# Delay_latch_stage.net
KiCad netlist of a schematic drawn in Altium Designer
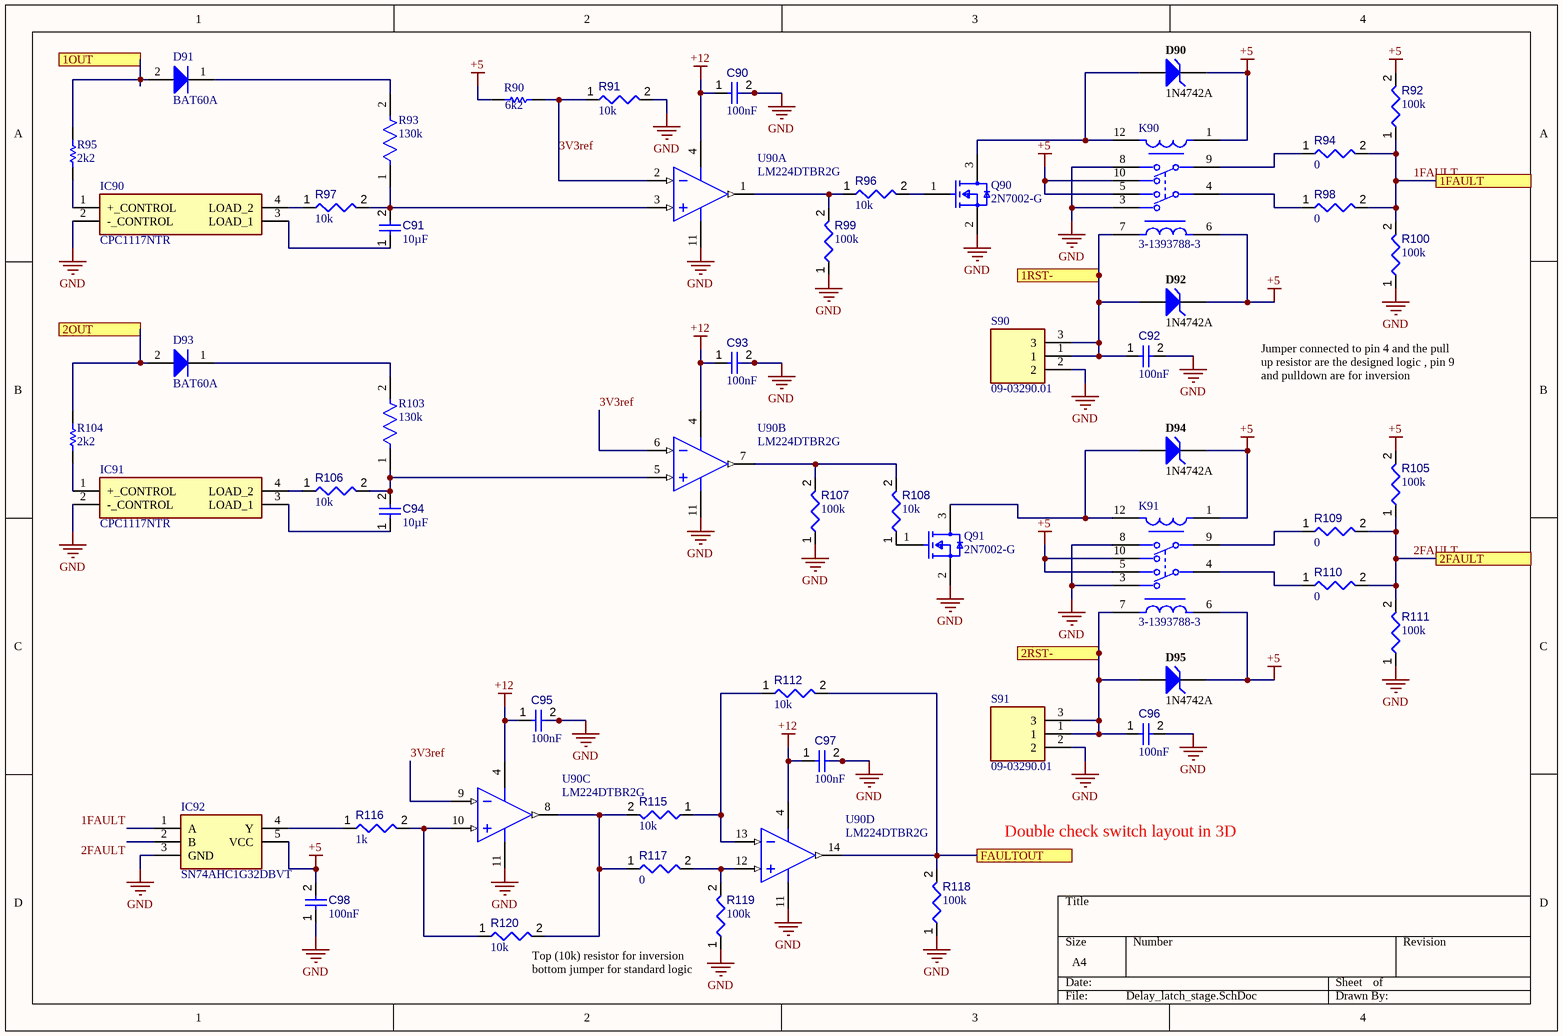
[diagram p0: Delay_latch_stage.SchDoc]

(export (version "E")
  (design (tool "Eeschema 10.0.6"))
  (components
    (comp (ref "C90")
      (value "100nF")
      (footprint "CAPC1608X90X40NL10T20")
      (description "Chip Capacitor, 100 nF, +/- 10%, 50 V, 0603 (1608 Metric)")
      (fields (field (name "TOLERANCE") "10%") (field (name "Comment") "Capacitor 100 nF +/-10% 50 V 0603"))
      (libsource (lib "UNSW Redback Racing") (part "CAP-NP-2"))
    )
    (comp (ref "C91")
      (value "10µF")
      (footprint "CAPC0603(1608)100_L")
      (description "Chip Capacitor, 10µF +/-20%, 10V, 0603, Thickness 1 mm")
      (fields (field (name "TOLERANCE") "10%") (field (name "Comment") "Capacitor 10µF +/-20% 10V 0603"))
      (libsource (lib "UNSW Redback Racing") (part "CAP-NP-2"))
    )
    (comp (ref "C92")
      (value "100nF")
      (footprint "CAPC1608X90X40NL10T20")
      (description "Chip Capacitor, 100 nF, +/- 10%, 50 V, 0603 (1608 Metric)")
      (fields (field (name "TOLERANCE") "10%") (field (name "Comment") "Capacitor 100 nF +/-10% 50 V 0603"))
      (libsource (lib "UNSW Redback Racing") (part "CAP-NP-2"))
    )
    (comp (ref "C93")
      (value "100nF")
      (footprint "CAPC1608X90X40NL10T20")
      (description "Chip Capacitor, 100 nF, +/- 10%, 50 V, 0603 (1608 Metric)")
      (fields (field (name "TOLERANCE") "10%") (field (name "Comment") "Capacitor 100 nF +/-10% 50 V 0603"))
      (libsource (lib "UNSW Redback Racing") (part "CAP-NP-2"))
    )
    (comp (ref "C94")
      (value "10µF")
      (footprint "CAPC0603(1608)100_L")
      (description "Chip Capacitor, 10µF +/-20%, 10V, 0603, Thickness 1 mm")
      (fields (field (name "TOLERANCE") "10%") (field (name "Comment") "Capacitor 10µF +/-20% 10V 0603"))
      (libsource (lib "UNSW Redback Racing") (part "CAP-NP-2"))
    )
    (comp (ref "C95")
      (value "100nF")
      (footprint "CAPC1608X90X40NL10T20")
      (description "Chip Capacitor, 100 nF, +/- 10%, 50 V, 0603 (1608 Metric)")
      (fields (field (name "TOLERANCE") "10%") (field (name "Comment") "Capacitor 100 nF +/-10% 50 V 0603"))
      (libsource (lib "UNSW Redback Racing") (part "CAP-NP-2"))
    )
    (comp (ref "C96")
      (value "100nF")
      (footprint "CAPC1608X90X40NL10T20")
      (description "Chip Capacitor, 100 nF, +/- 10%, 50 V, 0603 (1608 Metric)")
      (fields (field (name "TOLERANCE") "10%") (field (name "Comment") "Capacitor 100 nF +/-10% 50 V 0603"))
      (libsource (lib "UNSW Redback Racing") (part "CAP-NP-2"))
    )
    (comp (ref "C97")
      (value "100nF")
      (footprint "CAPC1608X90X40NL10T20")
      (description "Chip Capacitor, 100 nF, +/- 10%, 50 V, 0603 (1608 Metric)")
      (fields (field (name "TOLERANCE") "10%") (field (name "Comment") "Capacitor 100 nF +/-10% 50 V 0603"))
      (libsource (lib "UNSW Redback Racing") (part "CAP-NP-2"))
    )
    (comp (ref "C98")
      (value "100nF")
      (footprint "CAPC1608X90X40NL10T20")
      (description "Chip Capacitor, 100 nF, +/- 10%, 50 V, 0603 (1608 Metric)")
      (fields (field (name "TOLERANCE") "10%") (field (name "Comment") "Capacitor 100 nF +/-10% 50 V 0603"))
      (libsource (lib "UNSW Redback Racing") (part "CAP-NP-2"))
    )
    (comp (ref "D90")
      (value "1N4742A")
      (footprint "FAIR-DO-41-2_V")
      (description "Zener Diode, 12V, 1W, 5%, -65 to 200 degC, 2-Pin DO-41, Body 2.72 x 5.2 mm, RoHS")
      (fields (field (name "TOLERANCE") "5%") (field (name "MANUFACTURER") "Fairchild Semiconductor"))
      (libsource (lib "Altium Content Vault") (part "FAIR-DZEN-A1K2-2"))
    )
    (comp (ref "D91")
      (value "BAT60A")
      (footprint "INF-SOD323_V")
      (description "Silicon Schottky Diode, -55 to 85 degC, SOD323, Reel, Green")
      (fields (field (name "MANUFACTURER") "Infineon"))
      (libsource (lib "Altium Content Vault") (part "INF-D_K1A2-2"))
    )
    (comp (ref "D92")
      (value "1N4742A")
      (footprint "FAIR-DO-41-2_V")
      (description "Zener Diode, 12V, 1W, 5%, -65 to 200 degC, 2-Pin DO-41, Body 2.72 x 5.2 mm, RoHS")
      (fields (field (name "TOLERANCE") "5%") (field (name "MANUFACTURER") "Fairchild Semiconductor"))
      (libsource (lib "Altium Content Vault") (part "FAIR-DZEN-A1K2-2"))
    )
    (comp (ref "D93")
      (value "BAT60A")
      (footprint "INF-SOD323_V")
      (description "Silicon Schottky Diode, -55 to 85 degC, SOD323, Reel, Green")
      (fields (field (name "MANUFACTURER") "Infineon"))
      (libsource (lib "Altium Content Vault") (part "INF-D_K1A2-2"))
    )
    (comp (ref "D94")
      (value "1N4742A")
      (footprint "FAIR-DO-41-2_V")
      (description "Zener Diode, 12V, 1W, 5%, -65 to 200 degC, 2-Pin DO-41, Body 2.72 x 5.2 mm, RoHS")
      (fields (field (name "TOLERANCE") "5%") (field (name "MANUFACTURER") "Fairchild Semiconductor"))
      (libsource (lib "Altium Content Vault") (part "FAIR-DZEN-A1K2-2"))
    )
    (comp (ref "D95")
      (value "1N4742A")
      (footprint "FAIR-DO-41-2_V")
      (description "Zener Diode, 12V, 1W, 5%, -65 to 200 degC, 2-Pin DO-41, Body 2.72 x 5.2 mm, RoHS")
      (fields (field (name "TOLERANCE") "5%") (field (name "MANUFACTURER") "Fairchild Semiconductor"))
      (libsource (lib "Altium Content Vault") (part "FAIR-DZEN-A1K2-2"))
    )
    (comp (ref "IC90")
      (value "CPC1117NTR")
      (footprint "SamacSys:SOP254P610X216-4N")
      (description "Integrated Circuit")
      (fields (field (name "MOUSER2 PART NUMBER") "849-CPC1117NTR"))
      (libsource (lib "*") (part "CPC1117NTR"))
    )
    (comp (ref "IC91")
      (value "CPC1117NTR")
      (footprint "SamacSys:SOP254P610X216-4N")
      (description "Integrated Circuit")
      (fields (field (name "MOUSER2 PART NUMBER") "849-CPC1117NTR"))
      (libsource (lib "*") (part "CPC1117NTR"))
    )
    (comp (ref "IC92")
      (value "SN74AHC1G32DBVT")
      (footprint "SamacSys:SOT95P280X145-5N")
      (description "Integrated Circuit")
      (fields (field (name "MOUSER PART NUMBER") "595-SN74AHC1G32DBVT"))
      (libsource (lib "*") (part "SN74AHC1G32DBVT"))
    )
    (comp (ref "K90")
      (value "3-1393788-3")
      (footprint "FP-3-1393788-3-MFG")
      (description "RELAY GEN PURPOSE DPDT 2A 5VDC")
      (fields
        (field (name "OCTOPART") "https://octopart.com/3-1393788-3-te+connectivity-40665546")
        (field (name "MANUFACTURER") "TE Connectivity")
      )
      (libsource (lib "Altium Content Vault") (part "ac98cbd59e0863ff6ea4ecacfdd74e3"))
    )
    (comp (ref "K91")
      (value "3-1393788-3")
      (footprint "FP-3-1393788-3-MFG")
      (description "RELAY GEN PURPOSE DPDT 2A 5VDC")
      (fields
        (field (name "OCTOPART") "https://octopart.com/3-1393788-3-te+connectivity-40665546")
        (field (name "MANUFACTURER") "TE Connectivity")
      )
      (libsource (lib "Altium Content Vault") (part "ac98cbd59e0863ff6ea4ecacfdd74e3"))
    )
    (comp (ref "Q90")
      (value "2N7002-G")
      (footprint "FP-2N7002-G-IPC_C")
      (description "MOSFET N-CH 60V 0.115A SOT23-3")
      (fields
        (field (name "OCTOPART") "https://octopart.com/2n7002-g-microchip-47153309")
        (field (name "MANUFACTURER") "Microchip")
      )
      (libsource (lib "Altium Content Vault") (part "e719174c72bdd709d73c8feae40c216"))
    )
    (comp (ref "Q91")
      (value "2N7002-G")
      (footprint "FP-2N7002-G-IPC_C")
      (description "MOSFET N-CH 60V 0.115A SOT23-3")
      (fields
        (field (name "OCTOPART") "https://octopart.com/2n7002-g-microchip-47153309")
        (field (name "MANUFACTURER") "Microchip")
      )
      (libsource (lib "Altium Content Vault") (part "e719174c72bdd709d73c8feae40c216"))
    )
    (comp (ref "R90")
      (value "6k2")
      (footprint "RESC1609X50X30ML10T20")
      (fields (field (name "PART NUMBER") "CRCW06036K20FKEA") (field (name "MANUFACTURER") "Vishay Dale"))
      (libsource (lib "Altium Content Vault") (part "RES"))
    )
    (comp (ref "R91")
      (value "10k")
      (footprint "RESC1608X55X25ML10T15")
      (description "Chip Resistor, 10 KOhm, +/- 1%, 01 W, -55 to 155 degC, 0603 (1608 Metric)")
      (fields (field (name "POWER") "100mW") (field (name "TOLERANCE") "1%"))
      (libsource (lib "UNSW Redback Racing") (part "RES-2"))
    )
    (comp (ref "R92")
      (value "100k")
      (footprint "RESC1608X55X25ML10T15")
      (description "Chip Resistor, 100 KOhm, +/- 1%, 0.1 W, -55 to 155 degC, 0603 (1608 Metric)")
      (fields (field (name "TOLERANCE") "1%") (field (name "POWER") "100mW"))
      (libsource (lib "UNSW Redback Racing") (part "RES-2"))
    )
    (comp (ref "R93")
      (value "130k")
      (footprint "FP-CRCW0603-e3-IPC_C")
      (description "RES Thick Film, 130kΩ, 1%, 0.1W, 100ppm/°C, 0603")
      (fields (field (name "TOLERANCE") "1%"))
      (libsource (lib "Altium Content Vault") (part "1029c3af85768c4190bb7ad29bc67b5"))
    )
    (comp (ref "R94")
      (value "0")
      (footprint "RESC0603(1608)_L")
      (description "Jumper 0603 (1608 Metric)")
      (fields (field (name "Comment") "0R3J"))
      (libsource (lib "UNSW Redback Racing") (part "0R3J"))
    )
    (comp (ref "R95")
      (value "2k2")
      (footprint "RESC1608X55X25LL10T15")
      (fields (field (name "TOLERANCE") "1%") (field (name "MANUFACTURER") "Yageo"))
      (libsource (lib "Altium Content Vault") (part "RES-2"))
    )
    (comp (ref "R96")
      (value "10k")
      (footprint "RESC1608X55X25ML10T15")
      (description "Chip Resistor, 10 KOhm, +/- 1%, 01 W, -55 to 155 degC, 0603 (1608 Metric)")
      (fields (field (name "POWER") "100mW") (field (name "TOLERANCE") "1%"))
      (libsource (lib "UNSW Redback Racing") (part "RES-2"))
    )
    (comp (ref "R97")
      (value "10k")
      (footprint "RESC1608X55X25ML10T15")
      (description "Chip Resistor, 10 KOhm, +/- 1%, 01 W, -55 to 155 degC, 0603 (1608 Metric)")
      (fields (field (name "POWER") "100mW") (field (name "TOLERANCE") "1%"))
      (libsource (lib "UNSW Redback Racing") (part "RES-2"))
    )
    (comp (ref "R98")
      (value "0")
      (footprint "RESC0603(1608)_L")
      (description "Jumper 0603 (1608 Metric)")
      (fields (field (name "Comment") "0R3J"))
      (libsource (lib "UNSW Redback Racing") (part "0R3J"))
    )
    (comp (ref "R99")
      (value "100k")
      (footprint "RESC1608X55X25ML10T15")
      (description "Chip Resistor, 100 KOhm, +/- 1%, 0.1 W, -55 to 155 degC, 0603 (1608 Metric)")
      (fields (field (name "TOLERANCE") "1%") (field (name "POWER") "100mW"))
      (libsource (lib "UNSW Redback Racing") (part "RES-2"))
    )
    (comp (ref "R100")
      (value "100k")
      (footprint "RESC1608X55X25ML10T15")
      (description "Chip Resistor, 100 KOhm, +/- 1%, 0.1 W, -55 to 155 degC, 0603 (1608 Metric)")
      (fields (field (name "TOLERANCE") "1%") (field (name "POWER") "100mW"))
      (libsource (lib "UNSW Redback Racing") (part "RES-2"))
    )
    (comp (ref "R103")
      (value "130k")
      (footprint "FP-CRCW0603-e3-IPC_C")
      (description "RES Thick Film, 130kΩ, 1%, 0.1W, 100ppm/°C, 0603")
      (fields (field (name "TOLERANCE") "1%"))
      (libsource (lib "Altium Content Vault") (part "1029c3af85768c4190bb7ad29bc67b5"))
    )
    (comp (ref "R104")
      (value "2k2")
      (footprint "RESC1608X55X25LL10T15")
      (fields (field (name "TOLERANCE") "1%") (field (name "MANUFACTURER") "Yageo"))
      (libsource (lib "Altium Content Vault") (part "RES-2"))
    )
    (comp (ref "R105")
      (value "100k")
      (footprint "RESC1608X55X25ML10T15")
      (description "Chip Resistor, 100 KOhm, +/- 1%, 0.1 W, -55 to 155 degC, 0603 (1608 Metric)")
      (fields (field (name "TOLERANCE") "1%") (field (name "POWER") "100mW"))
      (libsource (lib "UNSW Redback Racing") (part "RES-2"))
    )
    (comp (ref "R106")
      (value "10k")
      (footprint "RESC1608X55X25ML10T15")
      (description "Chip Resistor, 10 KOhm, +/- 1%, 01 W, -55 to 155 degC, 0603 (1608 Metric)")
      (fields (field (name "POWER") "100mW") (field (name "TOLERANCE") "1%"))
      (libsource (lib "UNSW Redback Racing") (part "RES-2"))
    )
    (comp (ref "R107")
      (value "100k")
      (footprint "RESC1608X55X25ML10T15")
      (description "Chip Resistor, 100 KOhm, +/- 1%, 0.1 W, -55 to 155 degC, 0603 (1608 Metric)")
      (fields (field (name "TOLERANCE") "1%") (field (name "POWER") "100mW"))
      (libsource (lib "UNSW Redback Racing") (part "RES-2"))
    )
    (comp (ref "R108")
      (value "10k")
      (footprint "RESC1608X55X25ML10T15")
      (description "Chip Resistor, 10 KOhm, +/- 1%, 01 W, -55 to 155 degC, 0603 (1608 Metric)")
      (fields (field (name "POWER") "100mW") (field (name "TOLERANCE") "1%"))
      (libsource (lib "UNSW Redback Racing") (part "RES-2"))
    )
    (comp (ref "R109")
      (value "0")
      (footprint "RESC0603(1608)_L")
      (description "Jumper 0603 (1608 Metric)")
      (fields (field (name "Comment") "0R3J"))
      (libsource (lib "UNSW Redback Racing") (part "0R3J"))
    )
    (comp (ref "R110")
      (value "0")
      (footprint "RESC0603(1608)_L")
      (description "Jumper 0603 (1608 Metric)")
      (fields (field (name "Comment") "0R3J"))
      (libsource (lib "UNSW Redback Racing") (part "0R3J"))
    )
    (comp (ref "R111")
      (value "100k")
      (footprint "RESC1608X55X25ML10T15")
      (description "Chip Resistor, 100 KOhm, +/- 1%, 0.1 W, -55 to 155 degC, 0603 (1608 Metric)")
      (fields (field (name "TOLERANCE") "1%") (field (name "POWER") "100mW"))
      (libsource (lib "UNSW Redback Racing") (part "RES-2"))
    )
    (comp (ref "R112")
      (value "10k")
      (footprint "RESC1608X55X25ML10T15")
      (description "Chip Resistor, 10 KOhm, +/- 1%, 01 W, -55 to 155 degC, 0603 (1608 Metric)")
      (fields (field (name "POWER") "100mW") (field (name "TOLERANCE") "1%"))
      (libsource (lib "UNSW Redback Racing") (part "RES-2"))
    )
    (comp (ref "R115")
      (value "10k")
      (footprint "RESC1608X55X25ML10T15")
      (description "Chip Resistor, 10 KOhm, +/- 1%, 01 W, -55 to 155 degC, 0603 (1608 Metric)")
      (fields (field (name "POWER") "100mW") (field (name "TOLERANCE") "1%"))
      (libsource (lib "UNSW Redback Racing") (part "RES-2"))
    )
    (comp (ref "R116")
      (value "1k")
      (footprint "RESC1608X55X25ML10T15")
      (description "Chip Resistor, 1 KOhm, +/-1%, 0.1 W, -55 to 155 degC, 0603 (1608 Metric)")
      (fields (field (name "POWER") "100mW") (field (name "TOLERANCE") "1%"))
      (libsource (lib "UNSW Redback Racing") (part "RES-2"))
    )
    (comp (ref "R117")
      (value "0")
      (footprint "RESC0603(1608)_L")
      (description "Jumper 0603 (1608 Metric)")
      (fields (field (name "Comment") "0R3J"))
      (libsource (lib "UNSW Redback Racing") (part "0R3J"))
    )
    (comp (ref "R118")
      (value "100k")
      (footprint "RESC1608X55X25ML10T15")
      (description "Chip Resistor, 100 KOhm, +/- 1%, 0.1 W, -55 to 155 degC, 0603 (1608 Metric)")
      (fields (field (name "TOLERANCE") "1%") (field (name "POWER") "100mW"))
      (libsource (lib "UNSW Redback Racing") (part "RES-2"))
    )
    (comp (ref "R119")
      (value "100k")
      (footprint "RESC1608X55X25ML10T15")
      (description "Chip Resistor, 100 KOhm, +/- 1%, 0.1 W, -55 to 155 degC, 0603 (1608 Metric)")
      (fields (field (name "TOLERANCE") "1%") (field (name "POWER") "100mW"))
      (libsource (lib "UNSW Redback Racing") (part "RES-2"))
    )
    (comp (ref "R120")
      (value "10k")
      (footprint "RESC1608X55X25ML10T15")
      (description "Chip Resistor, 10 KOhm, +/- 1%, 01 W, -55 to 155 degC, 0603 (1608 Metric)")
      (fields (field (name "POWER") "100mW") (field (name "TOLERANCE") "1%"))
      (libsource (lib "UNSW Redback Racing") (part "RES-2"))
    )
    (comp (ref "S90")
      (value "09-03290.01")
      (footprint "SamacSys:09.03290.01")
      (description "Switch")
      (libsource (lib "*") (part "09-03290.01"))
    )
    (comp (ref "S91")
      (value "09-03290.01")
      (footprint "SamacSys:09.03290.01")
      (description "Switch")
      (libsource (lib "*") (part "09-03290.01"))
    )
    (comp (ref "U90")
      (value "LM224DTBR2G")
      (footprint "ONSC-TSSOP-14-948G-01_V")
      (fields (field (name "MANUFACTURER") "On Semiconductor"))
      (libsource (lib "Altium Content Vault") (part "ONSC-LM224_324_2902_NCV2902-14"))
    )
  )
  (nets
    (net (code "1") (name "+5") (class "Default")
      (node (ref "C98") (pin "2") (pinfunction "2_2") (pintype "passive"))
      (node (ref "D90") (pin "2") (pinfunction "K_2") (pintype "passive"))
      (node (ref "D92") (pin "2") (pinfunction "K_2") (pintype "passive"))
      (node (ref "D94") (pin "2") (pinfunction "K_2") (pintype "passive"))
      (node (ref "D95") (pin "2") (pinfunction "K_2") (pintype "passive"))
      (node (ref "IC92") (pin "5") (pinfunction "VCC_5") (pintype "passive"))
      (node (ref "K90") (pin "1") (pinfunction "set+/reset-_1") (pintype "passive"))
      (node (ref "K90") (pin "10") (pinfunction "10_10") (pintype "passive"))
      (node (ref "K90") (pin "5") (pinfunction "5_5") (pintype "passive"))
      (node (ref "K90") (pin "6") (pinfunction "reset+/set-_6") (pintype "passive"))
      (node (ref "K91") (pin "1") (pinfunction "set+/reset-_1") (pintype "passive"))
      (node (ref "K91") (pin "10") (pinfunction "10_10") (pintype "passive"))
      (node (ref "K91") (pin "5") (pinfunction "5_5") (pintype "passive"))
      (node (ref "K91") (pin "6") (pinfunction "reset+/set-_6") (pintype "passive"))
      (node (ref "R105") (pin "2") (pinfunction "2_2") (pintype "passive"))
      (node (ref "R90") (pin "1") (pinfunction "1_1") (pintype "passive"))
      (node (ref "R92") (pin "2") (pinfunction "2_2") (pintype "passive"))
    )
    (net (code "2") (name "+12") (class "Default")
      (node (ref "C90") (pin "1") (pinfunction "1_1") (pintype "passive"))
      (node (ref "C93") (pin "1") (pinfunction "1_1") (pintype "passive"))
      (node (ref "C95") (pin "1") (pinfunction "1_1") (pintype "passive"))
      (node (ref "C97") (pin "1") (pinfunction "1_1") (pintype "passive"))
      (node (ref "U90") (pin "4") (pinfunction "VCC_4") (pintype "power_in"))
    )
    (net (code "3") (name "/1FAULT") (class "Default")
      (node (ref "IC92") (pin "1") (pinfunction "A_1") (pintype "passive"))
      (node (ref "R100") (pin "2") (pinfunction "2_2") (pintype "passive"))
      (node (ref "R92") (pin "1") (pinfunction "1_1") (pintype "passive"))
      (node (ref "R94") (pin "2") (pinfunction "2_2") (pintype "passive"))
      (node (ref "R98") (pin "2") (pinfunction "2_2") (pintype "passive"))
    )
    (net (code "4") (name "/1OUT") (class "Default")
      (node (ref "D91") (pin "2") (pinfunction "A_2") (pintype "passive"))
      (node (ref "R95") (pin "2") (pinfunction "2_2") (pintype "passive"))
    )
    (net (code "5") (name "/1RST-") (class "Default")
      (node (ref "C92") (pin "1") (pinfunction "1_1") (pintype "passive"))
      (node (ref "D92") (pin "1") (pinfunction "A_1") (pintype "passive"))
      (node (ref "K90") (pin "7") (pinfunction "reset-/set+_7") (pintype "passive"))
      (node (ref "S90") (pin "1") (pinfunction "1_1") (pintype "passive"))
      (node (ref "S90") (pin "3") (pinfunction "3_3") (pintype "passive"))
    )
    (net (code "6") (name "/2FAULT") (class "Default")
      (node (ref "IC92") (pin "2") (pinfunction "B_2") (pintype "passive"))
      (node (ref "R105") (pin "1") (pinfunction "1_1") (pintype "passive"))
      (node (ref "R109") (pin "2") (pinfunction "2_2") (pintype "passive"))
      (node (ref "R110") (pin "2") (pinfunction "2_2") (pintype "passive"))
      (node (ref "R111") (pin "2") (pinfunction "2_2") (pintype "passive"))
    )
    (net (code "7") (name "/2OUT") (class "Default")
      (node (ref "D93") (pin "2") (pinfunction "A_2") (pintype "passive"))
      (node (ref "R104") (pin "2") (pinfunction "2_2") (pintype "passive"))
    )
    (net (code "8") (name "/2RST-") (class "Default")
      (node (ref "C96") (pin "1") (pinfunction "1_1") (pintype "passive"))
      (node (ref "D95") (pin "1") (pinfunction "A_1") (pintype "passive"))
      (node (ref "K91") (pin "7") (pinfunction "reset-/set+_7") (pintype "passive"))
      (node (ref "S91") (pin "1") (pinfunction "1_1") (pintype "passive"))
      (node (ref "S91") (pin "3") (pinfunction "3_3") (pintype "passive"))
    )
    (net (code "9") (name "/3V3ref") (class "Default")
      (node (ref "R90") (pin "2") (pinfunction "2_2") (pintype "passive"))
      (node (ref "R91") (pin "1") (pinfunction "1_1") (pintype "passive"))
      (node (ref "U90") (pin "2") (pinfunction "IN1-_2") (pintype "input"))
      (node (ref "U90") (pin "6") (pinfunction "IN2-_6") (pintype "input"))
      (node (ref "U90") (pin "9") (pinfunction "IN3-_9") (pintype "input"))
    )
    (net (code "10") (name "/FAULTOUT") (class "Default")
      (node (ref "R112") (pin "2") (pinfunction "2_2") (pintype "passive"))
      (node (ref "R118") (pin "2") (pinfunction "2_2") (pintype "passive"))
      (node (ref "U90") (pin "14") (pinfunction "OUT4_14") (pintype "output"))
    )
    (net (code "11") (name "GND") (class "Default")
      (node (ref "C90") (pin "2") (pinfunction "2_2") (pintype "passive"))
      (node (ref "C92") (pin "2") (pinfunction "2_2") (pintype "passive"))
      (node (ref "C93") (pin "2") (pinfunction "2_2") (pintype "passive"))
      (node (ref "C95") (pin "2") (pinfunction "2_2") (pintype "passive"))
      (node (ref "C96") (pin "2") (pinfunction "2_2") (pintype "passive"))
      (node (ref "C97") (pin "2") (pinfunction "2_2") (pintype "passive"))
      (node (ref "C98") (pin "1") (pinfunction "1_1") (pintype "passive"))
      (node (ref "IC90") (pin "2") (pinfunction "-_CONTROL_2") (pintype "passive"))
      (node (ref "IC91") (pin "2") (pinfunction "-_CONTROL_2") (pintype "passive"))
      (node (ref "IC92") (pin "3") (pinfunction "GND_3") (pintype "passive"))
      (node (ref "K90") (pin "3") (pinfunction "3_3") (pintype "passive"))
      (node (ref "K90") (pin "8") (pinfunction "8_8") (pintype "passive"))
      (node (ref "K91") (pin "3") (pinfunction "3_3") (pintype "passive"))
      (node (ref "K91") (pin "8") (pinfunction "8_8") (pintype "passive"))
      (node (ref "Q90") (pin "2") (pinfunction "SOURCE_2") (pintype "passive"))
      (node (ref "Q91") (pin "2") (pinfunction "SOURCE_2") (pintype "passive"))
      (node (ref "R100") (pin "1") (pinfunction "1_1") (pintype "passive"))
      (node (ref "R107") (pin "1") (pinfunction "1_1") (pintype "passive"))
      (node (ref "R111") (pin "1") (pinfunction "1_1") (pintype "passive"))
      (node (ref "R118") (pin "1") (pinfunction "1_1") (pintype "passive"))
      (node (ref "R119") (pin "1") (pinfunction "1_1") (pintype "passive"))
      (node (ref "R91") (pin "2") (pinfunction "2_2") (pintype "passive"))
      (node (ref "R99") (pin "1") (pinfunction "1_1") (pintype "passive"))
      (node (ref "S90") (pin "2") (pinfunction "2_2") (pintype "passive"))
      (node (ref "S91") (pin "2") (pinfunction "2_2") (pintype "passive"))
      (node (ref "U90") (pin "11") (pinfunction "VEE/GND_11") (pintype "power_in"))
    )
    (net (code "12") (name "Net-(D90-A)") (class "Default")
      (node (ref "D90") (pin "1") (pinfunction "A_1") (pintype "passive"))
      (node (ref "K90") (pin "12") (pinfunction "set-/reset+_12") (pintype "passive"))
      (node (ref "Q90") (pin "3") (pinfunction "DRAIN_3") (pintype "passive"))
    )
    (net (code "13") (name "Net-(D91-K)") (class "Default")
      (node (ref "D91") (pin "1") (pinfunction "K_1") (pintype "passive"))
      (node (ref "R93") (pin "2") (pinfunction "2_2") (pintype "passive"))
    )
    (net (code "14") (name "Net-(D93-K)") (class "Default")
      (node (ref "D93") (pin "1") (pinfunction "K_1") (pintype "passive"))
      (node (ref "R103") (pin "2") (pinfunction "2_2") (pintype "passive"))
    )
    (net (code "15") (name "Net-(D94-A)") (class "Default")
      (node (ref "D94") (pin "1") (pinfunction "A_1") (pintype "passive"))
      (node (ref "K91") (pin "12") (pinfunction "set-/reset+_12") (pintype "passive"))
      (node (ref "Q91") (pin "3") (pinfunction "DRAIN_3") (pintype "passive"))
    )
    (net (code "16") (name "Net-(IC90-+_CONTROL)") (class "Default")
      (node (ref "IC90") (pin "1") (pinfunction "+_CONTROL_1") (pintype "passive"))
      (node (ref "R95") (pin "1") (pinfunction "1_1") (pintype "passive"))
    )
    (net (code "17") (name "Net-(IC90-LOAD_1)") (class "Default")
      (node (ref "C91") (pin "1") (pinfunction "1_1") (pintype "passive"))
      (node (ref "IC90") (pin "3") (pinfunction "LOAD_1_3") (pintype "passive"))
    )
    (net (code "18") (name "Net-(IC90-LOAD_2)") (class "Default")
      (node (ref "IC90") (pin "4") (pinfunction "LOAD_2_4") (pintype "passive"))
      (node (ref "R97") (pin "1") (pinfunction "1_1") (pintype "passive"))
    )
    (net (code "19") (name "Net-(IC91-+_CONTROL)") (class "Default")
      (node (ref "IC91") (pin "1") (pinfunction "+_CONTROL_1") (pintype "passive"))
      (node (ref "R104") (pin "1") (pinfunction "1_1") (pintype "passive"))
    )
    (net (code "20") (name "Net-(IC91-LOAD_1)") (class "Default")
      (node (ref "C94") (pin "1") (pinfunction "1_1") (pintype "passive"))
      (node (ref "IC91") (pin "3") (pinfunction "LOAD_1_3") (pintype "passive"))
    )
    (net (code "21") (name "Net-(IC91-LOAD_2)") (class "Default")
      (node (ref "IC91") (pin "4") (pinfunction "LOAD_2_4") (pintype "passive"))
      (node (ref "R106") (pin "1") (pinfunction "1_1") (pintype "passive"))
    )
    (net (code "22") (name "Net-(IC92-Y)") (class "Default")
      (node (ref "IC92") (pin "4") (pinfunction "Y_4") (pintype "passive"))
      (node (ref "R116") (pin "1") (pinfunction "1_1") (pintype "passive"))
    )
    (net (code "23") (name "Net-(K90-Pad4)") (class "Default")
      (node (ref "K90") (pin "4") (pinfunction "4_4") (pintype "passive"))
      (node (ref "R98") (pin "1") (pinfunction "1_1") (pintype "passive"))
    )
    (net (code "24") (name "Net-(K90-Pad9)") (class "Default")
      (node (ref "K90") (pin "9") (pinfunction "9_9") (pintype "passive"))
      (node (ref "R94") (pin "1") (pinfunction "1_1") (pintype "passive"))
    )
    (net (code "25") (name "Net-(K91-Pad4)") (class "Default")
      (node (ref "K91") (pin "4") (pinfunction "4_4") (pintype "passive"))
      (node (ref "R110") (pin "1") (pinfunction "1_1") (pintype "passive"))
    )
    (net (code "26") (name "Net-(K91-Pad9)") (class "Default")
      (node (ref "K91") (pin "9") (pinfunction "9_9") (pintype "passive"))
      (node (ref "R109") (pin "1") (pinfunction "1_1") (pintype "passive"))
    )
    (net (code "27") (name "Net-(Q90-GATE)") (class "Default")
      (node (ref "Q90") (pin "1") (pinfunction "GATE_1") (pintype "passive"))
      (node (ref "R96") (pin "2") (pinfunction "2_2") (pintype "passive"))
    )
    (net (code "28") (name "Net-(Q91-GATE)") (class "Default")
      (node (ref "Q91") (pin "1") (pinfunction "GATE_1") (pintype "passive"))
      (node (ref "R108") (pin "1") (pinfunction "1_1") (pintype "passive"))
    )
    (net (code "29") (name "Net-(U90A-IN1+)") (class "Default")
      (node (ref "C91") (pin "2") (pinfunction "2_2") (pintype "passive"))
      (node (ref "R93") (pin "1") (pinfunction "1_1") (pintype "passive"))
      (node (ref "R97") (pin "2") (pinfunction "2_2") (pintype "passive"))
      (node (ref "U90") (pin "3") (pinfunction "IN1+_3") (pintype "input"))
    )
    (net (code "30") (name "Net-(U90A-OUT1)") (class "Default")
      (node (ref "R96") (pin "1") (pinfunction "1_1") (pintype "passive"))
      (node (ref "R99") (pin "2") (pinfunction "2_2") (pintype "passive"))
      (node (ref "U90") (pin "1") (pinfunction "OUT1_1") (pintype "output"))
    )
    (net (code "31") (name "Net-(U90B-IN2+)") (class "Default")
      (node (ref "C94") (pin "2") (pinfunction "2_2") (pintype "passive"))
      (node (ref "R103") (pin "1") (pinfunction "1_1") (pintype "passive"))
      (node (ref "R106") (pin "2") (pinfunction "2_2") (pintype "passive"))
      (node (ref "U90") (pin "5") (pinfunction "IN2+_5") (pintype "input"))
    )
    (net (code "32") (name "Net-(U90B-OUT2)") (class "Default")
      (node (ref "R107") (pin "2") (pinfunction "2_2") (pintype "passive"))
      (node (ref "R108") (pin "2") (pinfunction "2_2") (pintype "passive"))
      (node (ref "U90") (pin "7") (pinfunction "OUT2_7") (pintype "output"))
    )
    (net (code "33") (name "Net-(U90C-IN3+)") (class "Default")
      (node (ref "R116") (pin "2") (pinfunction "2_2") (pintype "passive"))
      (node (ref "R120") (pin "1") (pinfunction "1_1") (pintype "passive"))
      (node (ref "U90") (pin "10") (pinfunction "IN3+_10") (pintype "input"))
    )
    (net (code "34") (name "Net-(U90C-OUT3)") (class "Default")
      (node (ref "R115") (pin "2") (pinfunction "2_2") (pintype "passive"))
      (node (ref "R117") (pin "1") (pinfunction "1_1") (pintype "passive"))
      (node (ref "R120") (pin "2") (pinfunction "2_2") (pintype "passive"))
      (node (ref "U90") (pin "8") (pinfunction "OUT3_8") (pintype "output"))
    )
    (net (code "35") (name "Net-(U90D-IN4+)") (class "Default")
      (node (ref "R117") (pin "2") (pinfunction "2_2") (pintype "passive"))
      (node (ref "R119") (pin "2") (pinfunction "2_2") (pintype "passive"))
      (node (ref "U90") (pin "12") (pinfunction "IN4+_12") (pintype "input"))
    )
    (net (code "36") (name "Net-(U90D-IN4-)") (class "Default")
      (node (ref "R112") (pin "1") (pinfunction "1_1") (pintype "passive"))
      (node (ref "R115") (pin "1") (pinfunction "1_1") (pintype "passive"))
      (node (ref "U90") (pin "13") (pinfunction "IN4-_13") (pintype "input"))
    )
  )
)
